# CanSharkV20.net
KiCad netlist of a schematic drawn in EAGLE
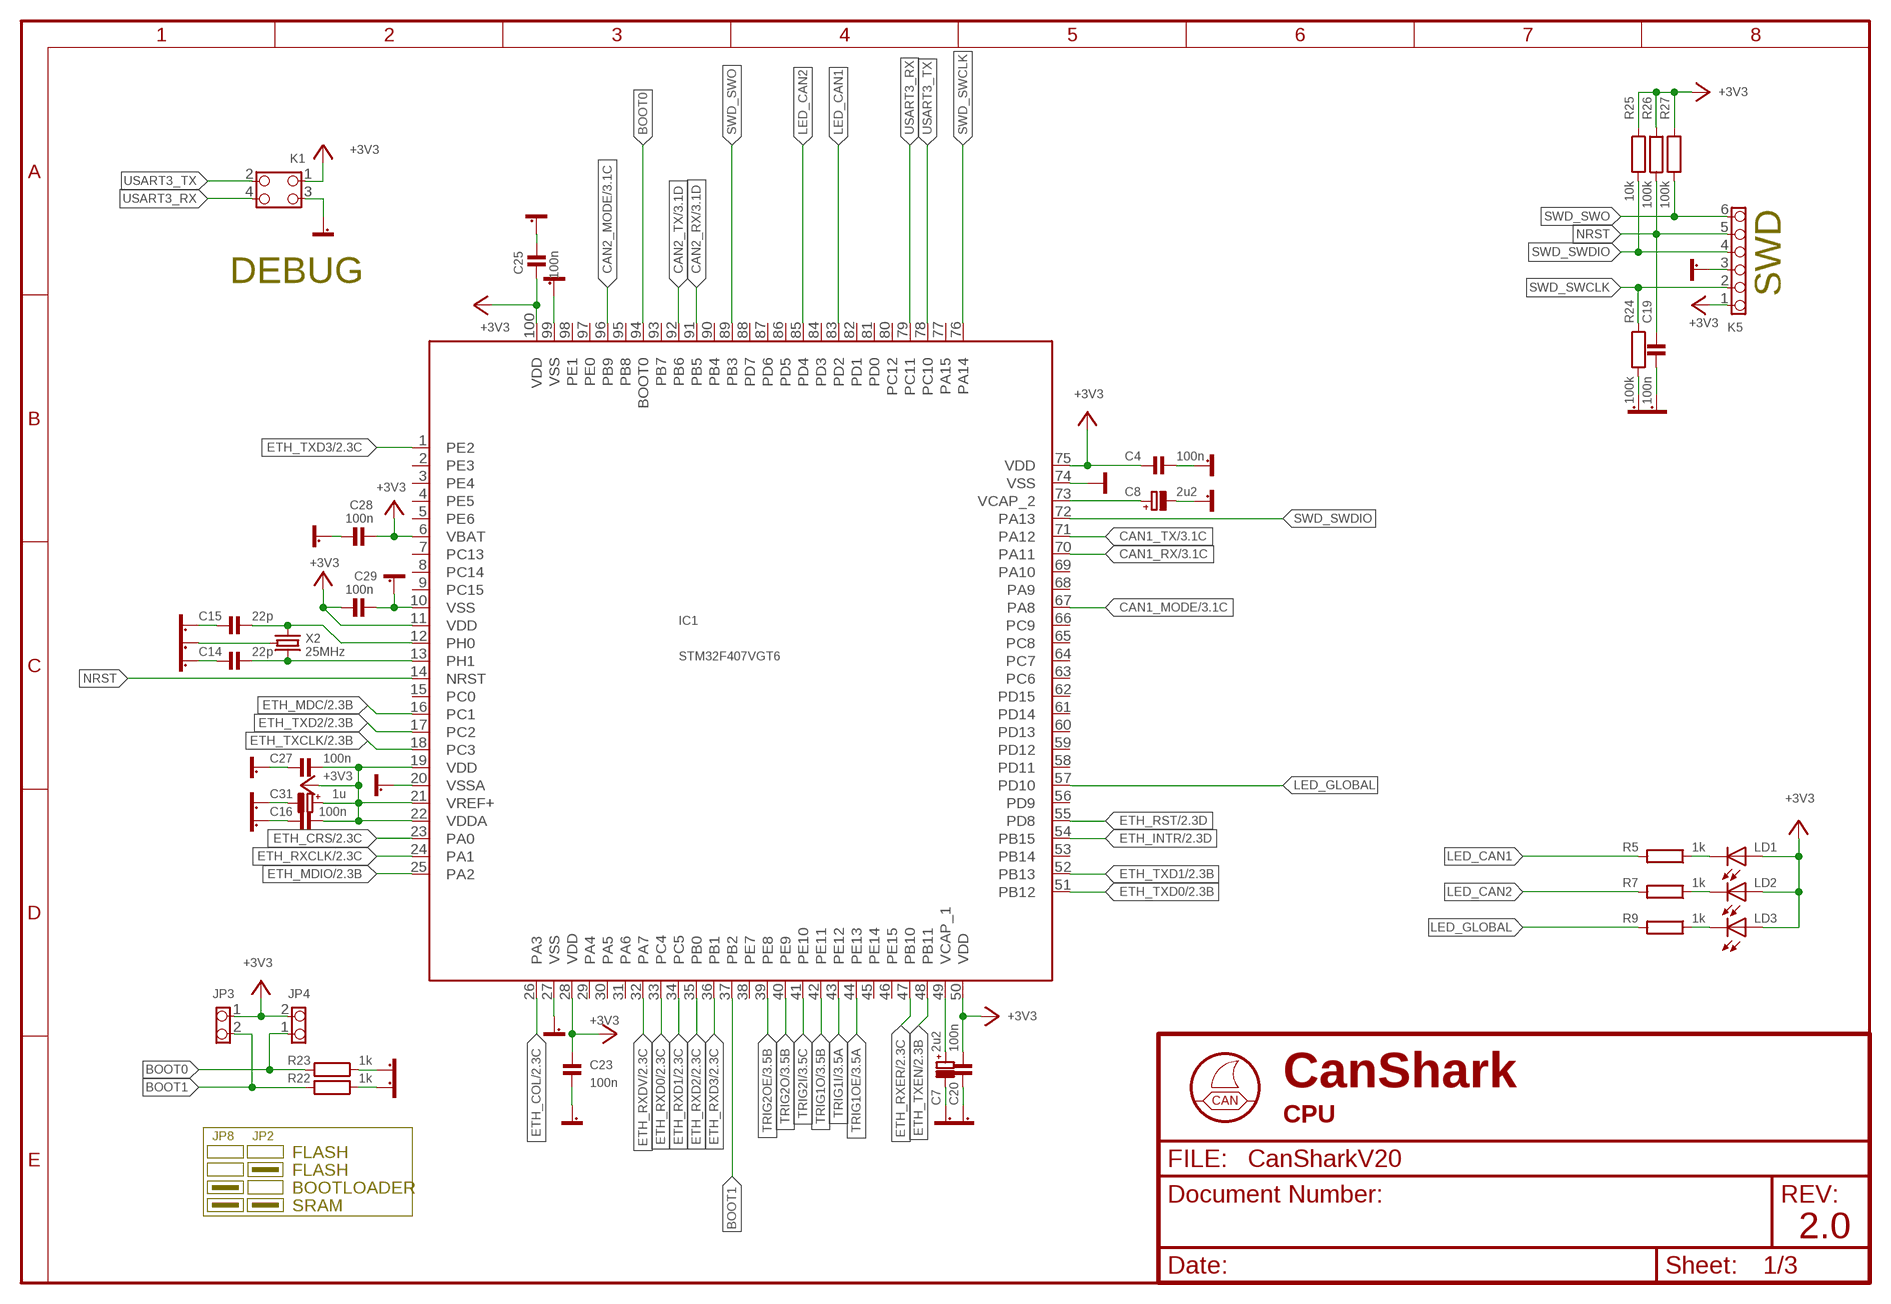
[diagram p0: schematic, sheet 1]
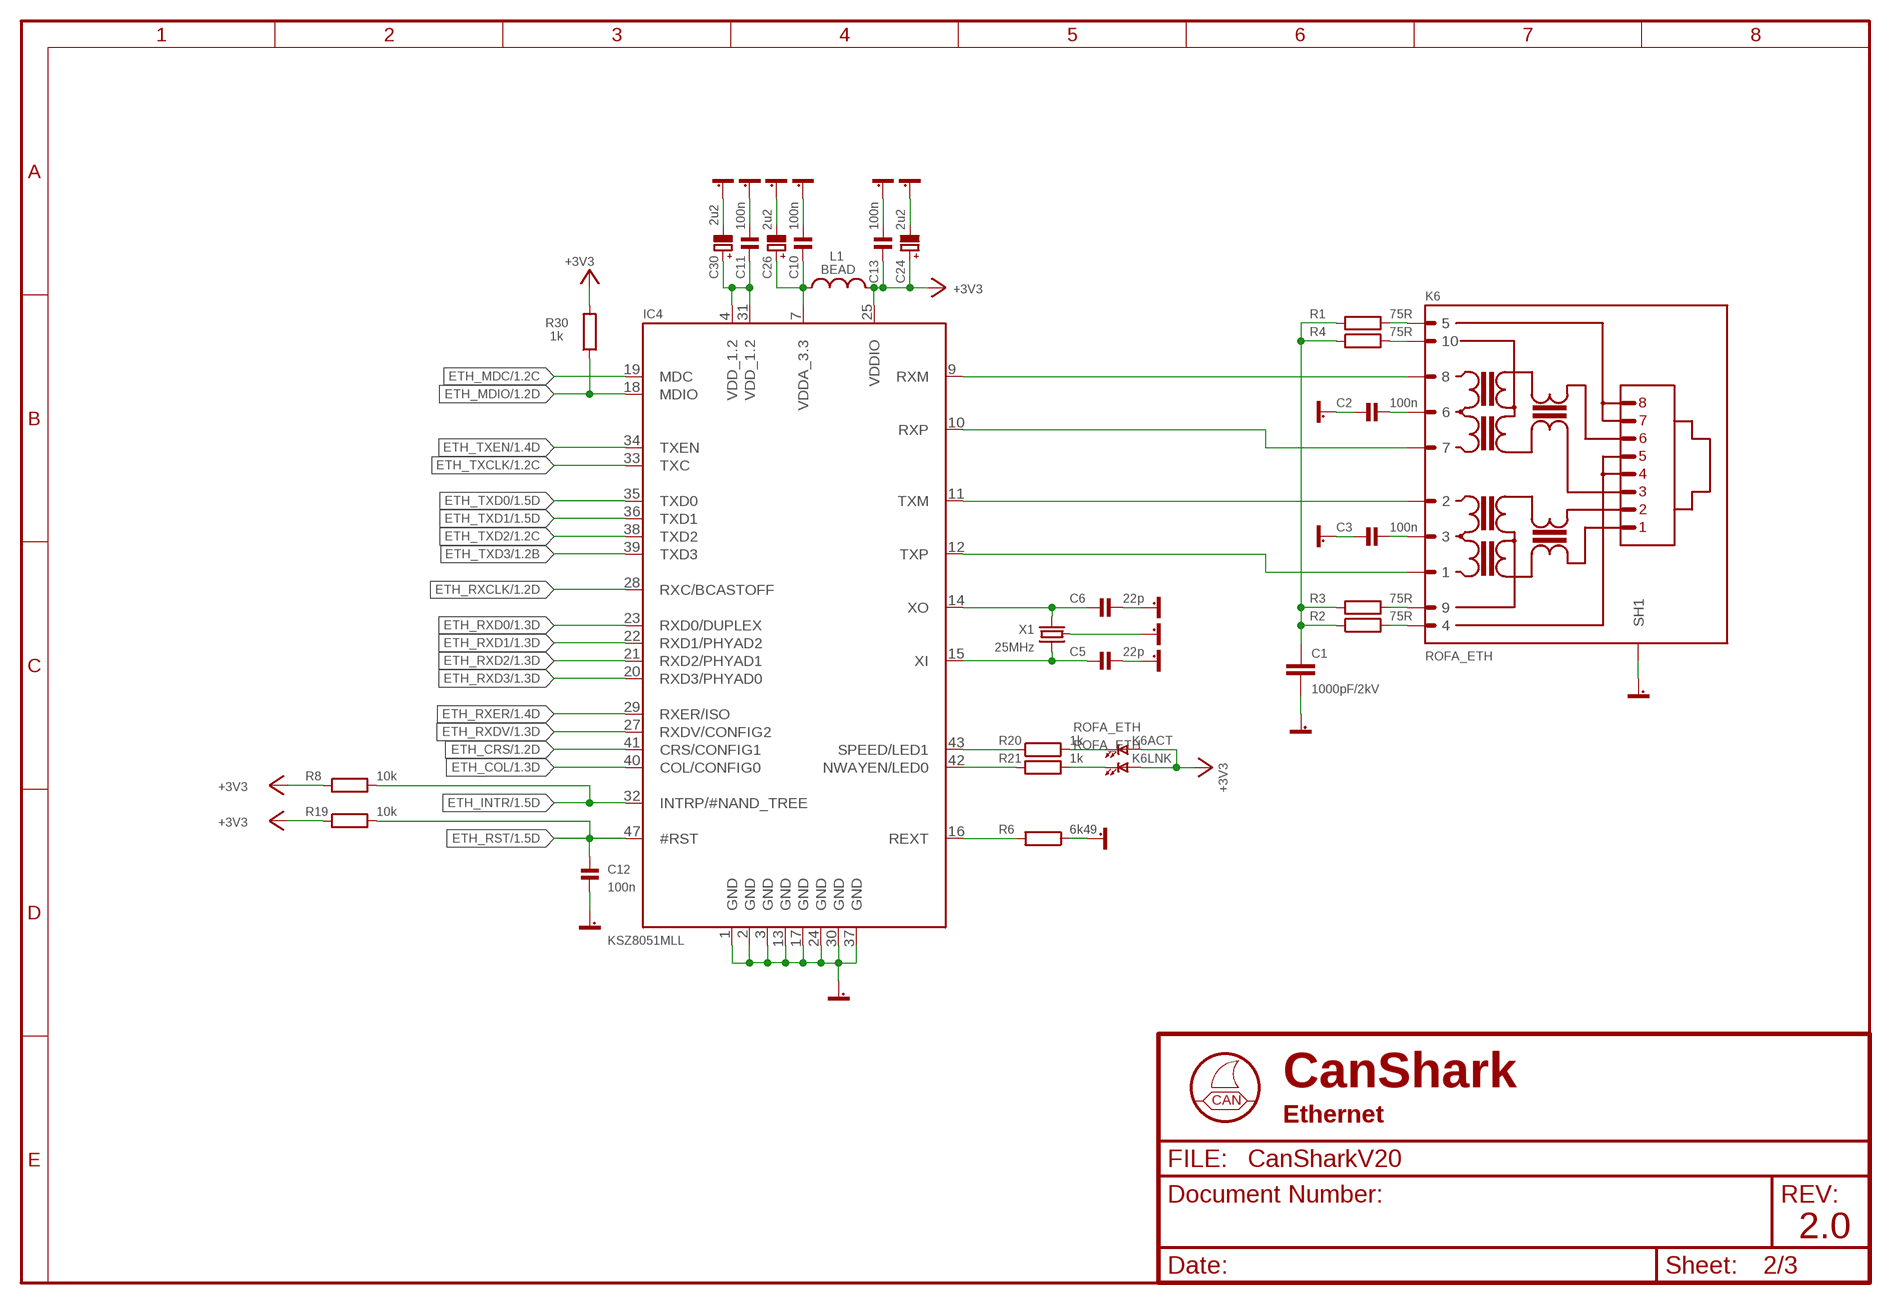
[diagram p1: schematic, sheet 2]
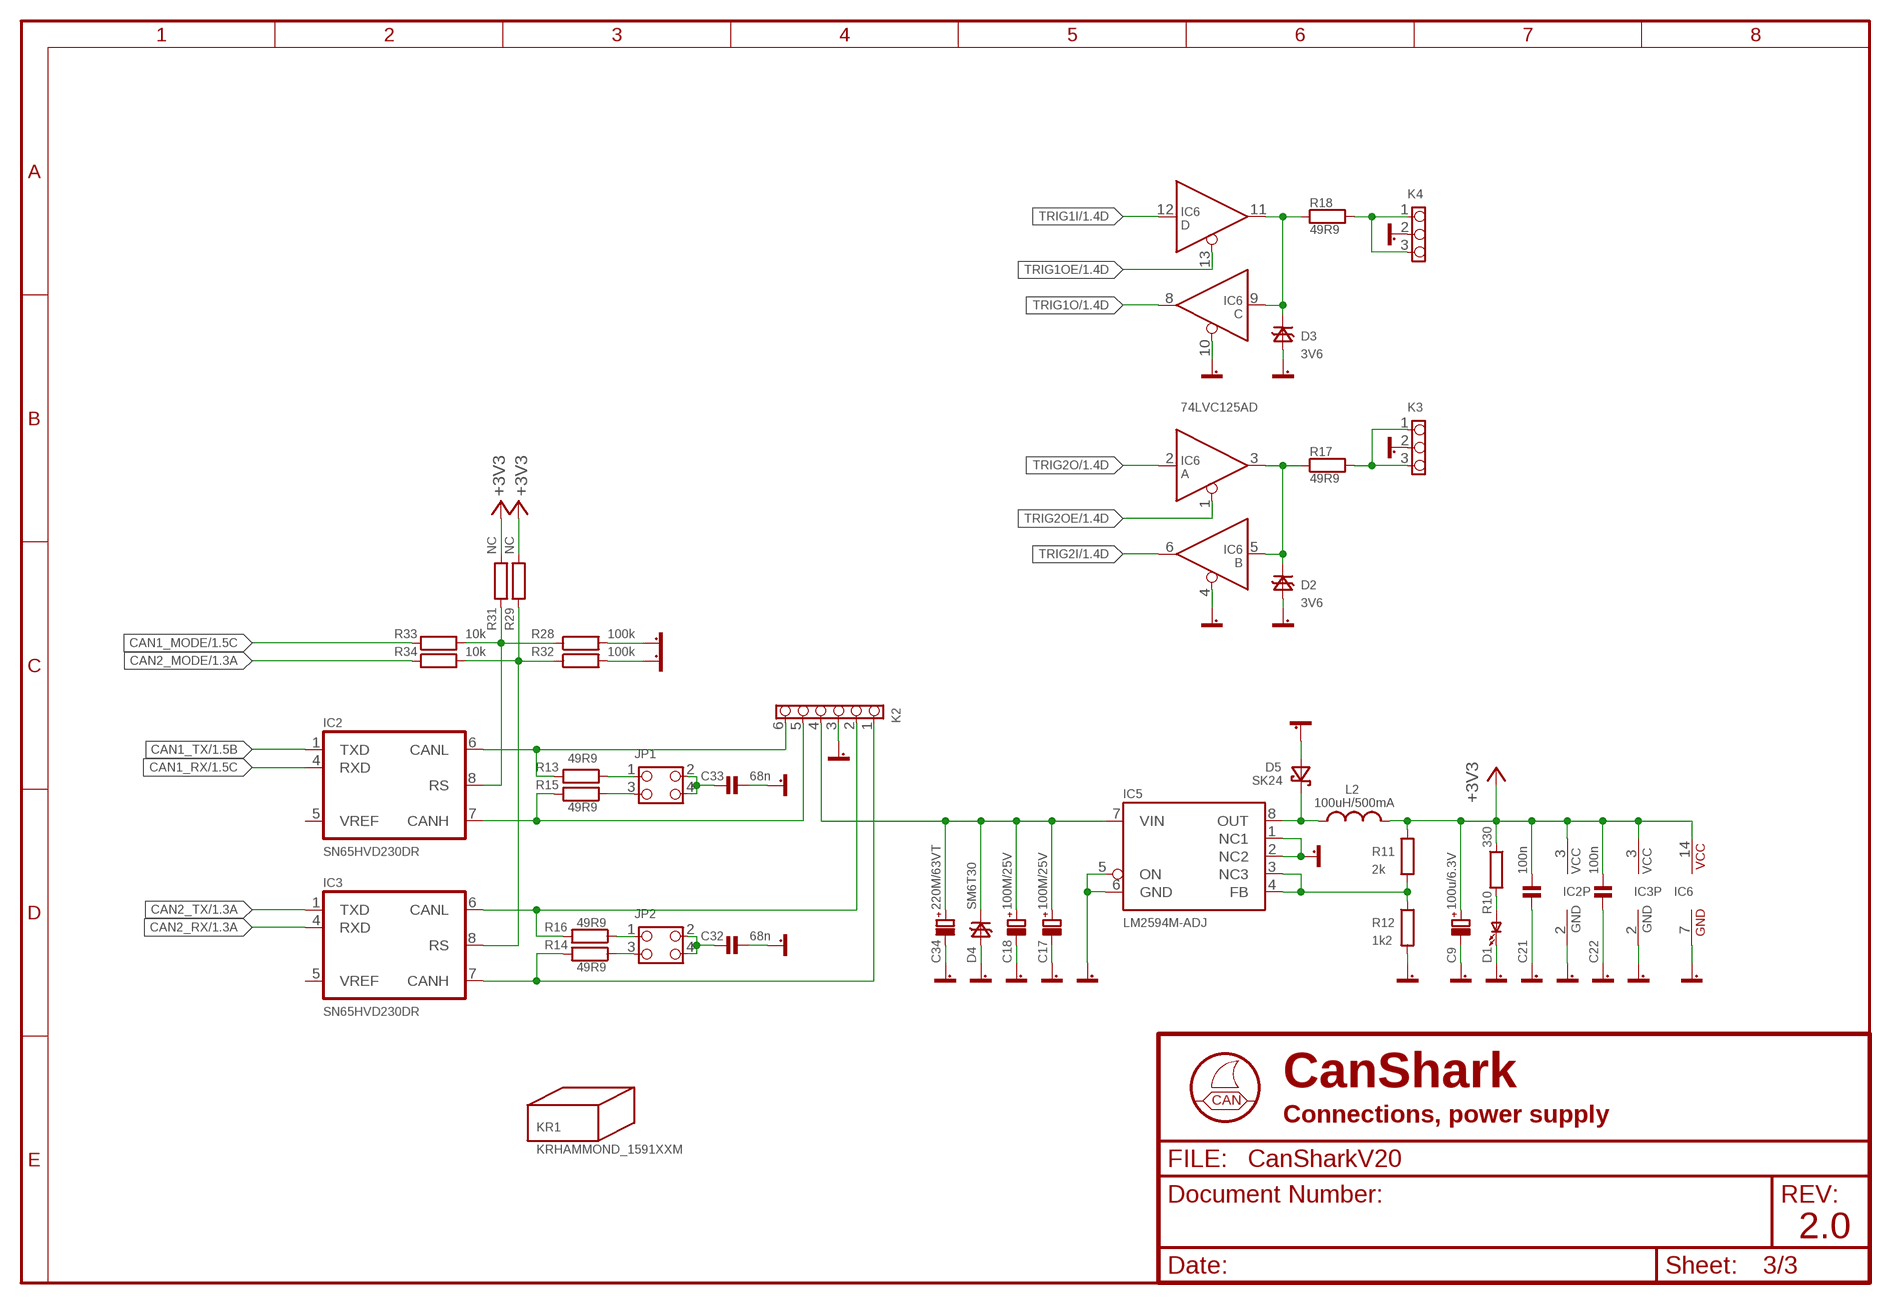
[diagram p2: schematic, sheet 3]

(export (version "E")
  (design (tool "Eeschema 10.0.6"))
  (components
    (comp (ref "C4")
      (value "100n")
      (footprint "eagle-import:0603")
      (libsource (lib "eagle-import") (part "C0603"))
    )
    (comp (ref "C7")
      (value "2u2")
      (footprint "eagle-import:CT3216A")
      (libsource (lib "eagle-import") (part "CECT3216"))
    )
    (comp (ref "C8")
      (value "2u2")
      (footprint "eagle-import:CT3216A")
      (libsource (lib "eagle-import") (part "CECT3216"))
    )
    (comp (ref "C14")
      (value "22p")
      (footprint "eagle-import:0603")
      (libsource (lib "eagle-import") (part "C0603"))
    )
    (comp (ref "C15")
      (value "22p")
      (footprint "eagle-import:0603")
      (libsource (lib "eagle-import") (part "C0603"))
    )
    (comp (ref "C16")
      (value "100n")
      (footprint "eagle-import:0603")
      (libsource (lib "eagle-import") (part "C0603"))
    )
    (comp (ref "C19")
      (value "100n")
      (footprint "eagle-import:0603")
      (libsource (lib "eagle-import") (part "C0603"))
    )
    (comp (ref "C20")
      (value "100n")
      (footprint "eagle-import:0603")
      (libsource (lib "eagle-import") (part "C0603"))
    )
    (comp (ref "C23")
      (value "100n")
      (footprint "eagle-import:0603")
      (libsource (lib "eagle-import") (part "C0603"))
    )
    (comp (ref "C25")
      (value "100n")
      (footprint "eagle-import:0603")
      (libsource (lib "eagle-import") (part "C0603"))
    )
    (comp (ref "C27")
      (value "100n")
      (footprint "eagle-import:0603")
      (libsource (lib "eagle-import") (part "C0603"))
    )
    (comp (ref "C28")
      (value "100n")
      (footprint "eagle-import:0603")
      (libsource (lib "eagle-import") (part "C0603"))
    )
    (comp (ref "C29")
      (value "100n")
      (footprint "eagle-import:0603")
      (libsource (lib "eagle-import") (part "C0603"))
    )
    (comp (ref "C31")
      (value "1u")
      (footprint "eagle-import:CT3216A")
      (libsource (lib "eagle-import") (part "CECT3216"))
    )
    (comp (ref "IC1")
      (value "STM32F407VGT6")
      (footprint "eagle-import:LQFP100")
      (libsource (lib "eagle-import") (part "STM32F4V07"))
    )
    (comp (ref "JP3")
      (value "PINHD-1X2")
      (footprint "eagle-import:1X02_254")
      (libsource (lib "eagle-import") (part "PINHD-1X2"))
    )
    (comp (ref "JP4")
      (value "PINHD-1X2")
      (footprint "eagle-import:1X02_254")
      (libsource (lib "eagle-import") (part "PINHD-1X2"))
    )
    (comp (ref "K1")
      (value "PINHD-2X2")
      (footprint "eagle-import:2X02_254")
      (libsource (lib "eagle-import") (part "PINHD-2X2"))
    )
    (comp (ref "K5")
      (value "PINHD-1X6")
      (footprint "eagle-import:1X06_254")
      (libsource (lib "eagle-import") (part "PINHD-1X6"))
    )
    (comp (ref "LD1")
      (value "TLLG4400")
      (footprint "eagle-import:LED3MM")
      (fields (field (name "MF") "VISHAY SEMICONDUCTOR"))
      (libsource (lib "eagle-import") (part "TLLG4400"))
    )
    (comp (ref "LD2")
      (value "TLLG4400")
      (footprint "eagle-import:LED3MM")
      (fields (field (name "MF") "VISHAY SEMICONDUCTOR"))
      (libsource (lib "eagle-import") (part "TLLG4400"))
    )
    (comp (ref "LD3")
      (value "TLLG4400")
      (footprint "eagle-import:LED3MM")
      (fields (field (name "MF") "VISHAY SEMICONDUCTOR"))
      (libsource (lib "eagle-import") (part "TLLG4400"))
    )
    (comp (ref "R5")
      (value "1k")
      (footprint "eagle-import:0603")
      (libsource (lib "eagle-import") (part "R_R0603"))
    )
    (comp (ref "R7")
      (value "1k")
      (footprint "eagle-import:0603")
      (libsource (lib "eagle-import") (part "R_R0603"))
    )
    (comp (ref "R9")
      (value "1k")
      (footprint "eagle-import:0603")
      (libsource (lib "eagle-import") (part "R_R0603"))
    )
    (comp (ref "R22")
      (value "1k")
      (footprint "eagle-import:0603")
      (libsource (lib "eagle-import") (part "R_R0603"))
    )
    (comp (ref "R23")
      (value "1k")
      (footprint "eagle-import:0603")
      (libsource (lib "eagle-import") (part "R_R0603"))
    )
    (comp (ref "R24")
      (value "100k")
      (footprint "eagle-import:0603")
      (libsource (lib "eagle-import") (part "R_R0603"))
    )
    (comp (ref "R25")
      (value "100k")
      (footprint "eagle-import:0603")
      (libsource (lib "eagle-import") (part "R_R0603"))
    )
    (comp (ref "R26")
      (value "10k")
      (footprint "eagle-import:0603")
      (libsource (lib "eagle-import") (part "R_R0603"))
    )
    (comp (ref "R27")
      (value "100k")
      (footprint "eagle-import:0603")
      (libsource (lib "eagle-import") (part "R_R0603"))
    )
    (comp (ref "X2")
      (value "25MHz")
      (footprint "eagle-import:X_XT324")
      (libsource (lib "eagle-import") (part "X_GND_XT324"))
    )
    (comp (ref "C1")
      (value "1000pF/2kV")
      (footprint "eagle-import:SMD1206")
      (libsource (lib "eagle-import") (part "KERAMICKYSMD1206"))
    )
    (comp (ref "C2")
      (value "100n")
      (footprint "eagle-import:0603")
      (libsource (lib "eagle-import") (part "C0603"))
    )
    (comp (ref "C3")
      (value "100n")
      (footprint "eagle-import:0603")
      (libsource (lib "eagle-import") (part "C0603"))
    )
    (comp (ref "C5")
      (value "22p")
      (footprint "eagle-import:0603")
      (libsource (lib "eagle-import") (part "C0603"))
    )
    (comp (ref "C6")
      (value "22p")
      (footprint "eagle-import:0603")
      (libsource (lib "eagle-import") (part "C0603"))
    )
    (comp (ref "C10")
      (value "100n")
      (footprint "eagle-import:0603")
      (libsource (lib "eagle-import") (part "C0603"))
    )
    (comp (ref "C11")
      (value "100n")
      (footprint "eagle-import:0603")
      (libsource (lib "eagle-import") (part "C0603"))
    )
    (comp (ref "C12")
      (value "100n")
      (footprint "eagle-import:0603")
      (libsource (lib "eagle-import") (part "C0603"))
    )
    (comp (ref "C13")
      (value "100n")
      (footprint "eagle-import:0603")
      (libsource (lib "eagle-import") (part "C0603"))
    )
    (comp (ref "C24")
      (value "2u2")
      (footprint "eagle-import:CT3216A")
      (libsource (lib "eagle-import") (part "CECT3216"))
    )
    (comp (ref "C26")
      (value "2u2")
      (footprint "eagle-import:CT3216A")
      (libsource (lib "eagle-import") (part "CECT3216"))
    )
    (comp (ref "C30")
      (value "2u2")
      (footprint "eagle-import:CT3216A")
      (libsource (lib "eagle-import") (part "CECT3216"))
    )
    (comp (ref "IC4")
      (value "KSZ8051MLL")
      (footprint "eagle-import:LQFP48")
      (libsource (lib "eagle-import") (part "KSZ8051MLL"))
    )
    (comp (ref "K6")
      (value "ROFA_ETH")
      (footprint "eagle-import:RJ45_TRAFO")
      (libsource (lib "eagle-import") (part "RJ45_TRAFO"))
    )
    (comp (ref "L1")
      (value "BEAD")
      (footprint "eagle-import:1206")
      (libsource (lib "eagle-import") (part "L1206"))
    )
    (comp (ref "R1")
      (value "75R")
      (footprint "eagle-import:0603")
      (libsource (lib "eagle-import") (part "R_R0603"))
    )
    (comp (ref "R2")
      (value "75R")
      (footprint "eagle-import:0603")
      (libsource (lib "eagle-import") (part "R_R0603"))
    )
    (comp (ref "R3")
      (value "75R")
      (footprint "eagle-import:0603")
      (libsource (lib "eagle-import") (part "R_R0603"))
    )
    (comp (ref "R4")
      (value "75R")
      (footprint "eagle-import:0603")
      (libsource (lib "eagle-import") (part "R_R0603"))
    )
    (comp (ref "R6")
      (value "6k49")
      (footprint "eagle-import:0603")
      (libsource (lib "eagle-import") (part "R_R0603"))
    )
    (comp (ref "R8")
      (value "10k")
      (footprint "eagle-import:0603")
      (libsource (lib "eagle-import") (part "R_R0603"))
    )
    (comp (ref "R19")
      (value "10k")
      (footprint "eagle-import:0603")
      (libsource (lib "eagle-import") (part "R_R0603"))
    )
    (comp (ref "R20")
      (value "1k")
      (footprint "eagle-import:0603")
      (libsource (lib "eagle-import") (part "R_R0603"))
    )
    (comp (ref "R21")
      (value "1k")
      (footprint "eagle-import:0603")
      (libsource (lib "eagle-import") (part "R_R0603"))
    )
    (comp (ref "R30")
      (value "1k")
      (footprint "eagle-import:0603")
      (libsource (lib "eagle-import") (part "R_R0603"))
    )
    (comp (ref "X1")
      (value "25MHz")
      (footprint "eagle-import:X_XT324")
      (libsource (lib "eagle-import") (part "X_GND_XT324"))
    )
    (comp (ref "C9")
      (value "100u/6.3V")
      (footprint "eagle-import:CT3528B")
      (libsource (lib "eagle-import") (part "CECT3528"))
    )
    (comp (ref "C17")
      (value "100M/25V")
      (footprint "eagle-import:CT7343D")
      (libsource (lib "eagle-import") (part "CECT7343"))
    )
    (comp (ref "C18")
      (value "100M/25V")
      (footprint "eagle-import:CT7343D")
      (libsource (lib "eagle-import") (part "CECT7343"))
    )
    (comp (ref "C21")
      (value "100n")
      (footprint "eagle-import:0603")
      (libsource (lib "eagle-import") (part "C0603"))
    )
    (comp (ref "C22")
      (value "100n")
      (footprint "eagle-import:0603")
      (libsource (lib "eagle-import") (part "C0603"))
    )
    (comp (ref "C32")
      (value "68n")
      (footprint "eagle-import:0805")
      (libsource (lib "eagle-import") (part "C0805"))
    )
    (comp (ref "C33")
      (value "68n")
      (footprint "eagle-import:0805")
      (libsource (lib "eagle-import") (part "C0805"))
    )
    (comp (ref "C34")
      (value "220M/63VT")
      (footprint "eagle-import:CE_D10L13_R")
      (libsource (lib "eagle-import") (part "CE_D10L13_R"))
    )
    (comp (ref "D1")
      (value "LED0805")
      (footprint "eagle-import:LED_0805")
      (libsource (lib "eagle-import") (part "LED0805"))
    )
    (comp (ref "D2")
      (value "3V6")
      (footprint "eagle-import:D_SMA")
      (libsource (lib "eagle-import") (part "!discrete_D_TRANSIL_SMA"))
    )
    (comp (ref "D3")
      (value "3V6")
      (footprint "eagle-import:D_SMA")
      (libsource (lib "eagle-import") (part "!discrete_D_TRANSIL_SMA"))
    )
    (comp (ref "D4")
      (value "SM6T30")
      (footprint "eagle-import:D_SMB")
      (libsource (lib "eagle-import") (part "D_TRANSIL_SMB"))
    )
    (comp (ref "D5")
      (value "SK24")
      (footprint "eagle-import:D_SMB")
      (libsource (lib "eagle-import") (part "D_SCHOTKY_SMB"))
    )
    (comp (ref "IC2")
      (value "SN65HVD230DR")
      (footprint "eagle-import:SO08")
      (libsource (lib "eagle-import") (part "MCP2551/S"))
    )
    (comp (ref "IC3")
      (value "SN65HVD230DR")
      (footprint "eagle-import:SO08")
      (libsource (lib "eagle-import") (part "MCP2551/S"))
    )
    (comp (ref "IC5")
      (value "LM2594M-ADJ")
      (footprint "eagle-import:SO08")
      (libsource (lib "eagle-import") (part "LM2594_SO"))
    )
    (comp (ref "IC6")
      (value "74LVC125AD")
      (footprint "eagle-import:SO14")
      (libsource (lib "eagle-import") (part "74125ADLVC"))
    )
    (comp (ref "JP1")
      (value "PINHD-2X2_254_EDGE")
      (footprint "eagle-import:2X02_254_EDGE")
      (libsource (lib "eagle-import") (part "PINHD-2X2_254_EDGE"))
    )
    (comp (ref "JP2")
      (value "PINHD-2X2_254_EDGE")
      (footprint "eagle-import:2X02_254_EDGE")
      (libsource (lib "eagle-import") (part "PINHD-2X2_254_EDGE"))
    )
    (comp (ref "K2")
      (value "PINHD-1X6_381_V")
      (footprint "eagle-import:1X06_381_V")
      (libsource (lib "eagle-import") (part "PINHD-1X6_381_V"))
    )
    (comp (ref "K3")
      (value "PINHD-1X3")
      (footprint "eagle-import:1X03_254")
      (libsource (lib "eagle-import") (part "PINHD-1X3"))
    )
    (comp (ref "K4")
      (value "PINHD-1X3")
      (footprint "eagle-import:1X03_254")
      (libsource (lib "eagle-import") (part "PINHD-1X3"))
    )
    (comp (ref "KR1")
      (value "KRHAMMOND_1591XXM")
      (footprint "eagle-import:HAMMOND_1591XXM")
      (libsource (lib "eagle-import") (part "KRHAMMOND_1591XXM"))
    )
    (comp (ref "L2")
      (value "100uH/500mA")
      (footprint "eagle-import:L_MLC12XX")
      (libsource (lib "eagle-import") (part "L_MLC12XX"))
    )
    (comp (ref "R10")
      (value "330")
      (footprint "eagle-import:0603")
      (libsource (lib "eagle-import") (part "R_R0603"))
    )
    (comp (ref "R11")
      (value "2k")
      (footprint "eagle-import:0603")
      (libsource (lib "eagle-import") (part "R_R0603"))
    )
    (comp (ref "R12")
      (value "1k2")
      (footprint "eagle-import:0603")
      (libsource (lib "eagle-import") (part "R_R0603"))
    )
    (comp (ref "R13")
      (value "49R9")
      (footprint "eagle-import:0805")
      (libsource (lib "eagle-import") (part "R_R0805"))
    )
    (comp (ref "R14")
      (value "49R9")
      (footprint "eagle-import:0805")
      (libsource (lib "eagle-import") (part "R_R0805"))
    )
    (comp (ref "R15")
      (value "49R9")
      (footprint "eagle-import:0805")
      (libsource (lib "eagle-import") (part "R_R0805"))
    )
    (comp (ref "R16")
      (value "49R9")
      (footprint "eagle-import:0805")
      (libsource (lib "eagle-import") (part "R_R0805"))
    )
    (comp (ref "R17")
      (value "49R9")
      (footprint "eagle-import:0805")
      (libsource (lib "eagle-import") (part "R_R0805"))
    )
    (comp (ref "R18")
      (value "49R9")
      (footprint "eagle-import:0805")
      (libsource (lib "eagle-import") (part "R_R0805"))
    )
    (comp (ref "R28")
      (value "100k")
      (footprint "eagle-import:0603")
      (libsource (lib "eagle-import") (part "R_R0603"))
    )
    (comp (ref "R29")
      (value "NC")
      (footprint "eagle-import:0603")
      (libsource (lib "eagle-import") (part "R_R0603"))
    )
    (comp (ref "R31")
      (value "NC")
      (footprint "eagle-import:0603")
      (libsource (lib "eagle-import") (part "R_R0603"))
    )
    (comp (ref "R32")
      (value "100k")
      (footprint "eagle-import:0603")
      (libsource (lib "eagle-import") (part "R_R0603"))
    )
    (comp (ref "R33")
      (value "10k")
      (footprint "eagle-import:0603")
      (libsource (lib "eagle-import") (part "R_R0603"))
    )
    (comp (ref "R34")
      (value "10k")
      (footprint "eagle-import:0603")
      (libsource (lib "eagle-import") (part "R_R0603"))
    )
  )
  (nets
    (net (code "1") (name "+3V3") (class "Default")
      (node (ref "C13") (pin "2") (pinfunction "2_2") (pintype "passive"))
      (node (ref "C16") (pin "1") (pinfunction "1_1") (pintype "passive"))
      (node (ref "C20") (pin "1") (pinfunction "1_1") (pintype "passive"))
      (node (ref "C21") (pin "1") (pinfunction "1_1") (pintype "passive"))
      (node (ref "C22") (pin "1") (pinfunction "1_1") (pintype "passive"))
      (node (ref "C23") (pin "1") (pinfunction "1_1") (pintype "passive"))
      (node (ref "C24") (pin "+") (pinfunction "+_+") (pintype "passive"))
      (node (ref "C25") (pin "2") (pinfunction "2_2") (pintype "passive"))
      (node (ref "C27") (pin "1") (pinfunction "1_1") (pintype "passive"))
      (node (ref "C28") (pin "2") (pinfunction "2_2") (pintype "passive"))
      (node (ref "C29") (pin "2") (pinfunction "2_2") (pintype "passive"))
      (node (ref "C31") (pin "+") (pinfunction "+_+") (pintype "passive"))
      (node (ref "C4") (pin "2") (pinfunction "2_2") (pintype "passive"))
      (node (ref "C9") (pin "+") (pinfunction "+_+") (pintype "passive"))
      (node (ref "IC1") (pin "100") (pinfunction "VDD_100") (pintype "passive"))
      (node (ref "IC1") (pin "11") (pinfunction "VDD_11") (pintype "passive"))
      (node (ref "IC1") (pin "19") (pinfunction "VDD_19") (pintype "passive"))
      (node (ref "IC1") (pin "21") (pinfunction "VREF+_21") (pintype "passive"))
      (node (ref "IC1") (pin "22") (pinfunction "VDDA_22") (pintype "passive"))
      (node (ref "IC1") (pin "28") (pinfunction "VDD_28") (pintype "passive"))
      (node (ref "IC1") (pin "50") (pinfunction "VDD_50") (pintype "passive"))
      (node (ref "IC1") (pin "6") (pinfunction "VBAT_6") (pintype "passive"))
      (node (ref "IC1") (pin "75") (pinfunction "VDD_75") (pintype "passive"))
      (node (ref "IC2") (pin "3") (pinfunction "VCC_3") (pintype "power_in"))
      (node (ref "IC3") (pin "3") (pinfunction "VCC_3") (pintype "power_in"))
      (node (ref "IC4") (pin "25") (pinfunction "VDDIO_25") (pintype "passive"))
      (node (ref "IC6") (pin "14") (pinfunction "VCC_14") (pintype "passive"))
      (node (ref "JP3") (pin "1") (pinfunction "1_1") (pintype "passive"))
      (node (ref "JP4") (pin "2") (pinfunction "2_2") (pintype "passive"))
      (node (ref "K1") (pin "1") (pinfunction "1_1") (pintype "passive"))
      (node (ref "K5") (pin "1") (pinfunction "1_1") (pintype "passive"))
      (node (ref "K6") (pin "A_G") (pinfunction "A_A_G") (pintype "passive"))
      (node (ref "K6") (pin "A_Y") (pinfunction "A_A_Y") (pintype "passive"))
      (node (ref "L1") (pin "1") (pinfunction "1_1") (pintype "passive"))
      (node (ref "L2") (pin "2") (pinfunction "1_2") (pintype "passive"))
      (node (ref "LD1") (pin "A") (pinfunction "A_A") (pintype "passive"))
      (node (ref "LD2") (pin "A") (pinfunction "A_A") (pintype "passive"))
      (node (ref "LD3") (pin "A") (pinfunction "A_A") (pintype "passive"))
      (node (ref "R10") (pin "1") (pinfunction "1_1") (pintype "passive"))
      (node (ref "R11") (pin "1") (pinfunction "1_1") (pintype "passive"))
      (node (ref "R19") (pin "1") (pinfunction "1_1") (pintype "passive"))
      (node (ref "R25") (pin "1") (pinfunction "1_1") (pintype "passive"))
      (node (ref "R26") (pin "2") (pinfunction "2_2") (pintype "passive"))
      (node (ref "R27") (pin "1") (pinfunction "1_1") (pintype "passive"))
      (node (ref "R29") (pin "1") (pinfunction "1_1") (pintype "passive"))
      (node (ref "R30") (pin "2") (pinfunction "2_2") (pintype "passive"))
      (node (ref "R31") (pin "1") (pinfunction "1_1") (pintype "passive"))
      (node (ref "R8") (pin "1") (pinfunction "1_1") (pintype "passive"))
    )
    (net (code "2") (name "BOOT0") (class "Default")
      (node (ref "IC1") (pin "94") (pinfunction "BOOT0_94") (pintype "passive"))
      (node (ref "JP4") (pin "1") (pinfunction "1_1") (pintype "passive"))
      (node (ref "R23") (pin "2") (pinfunction "2_2") (pintype "passive"))
    )
    (net (code "3") (name "BOOT1") (class "Default")
      (node (ref "IC1") (pin "37") (pinfunction "PB2_37") (pintype "passive"))
      (node (ref "JP3") (pin "2") (pinfunction "2_2") (pintype "passive"))
      (node (ref "R22") (pin "2") (pinfunction "2_2") (pintype "passive"))
    )
    (net (code "4") (name "CAN1_MODE") (class "Default")
      (node (ref "IC1") (pin "67") (pinfunction "PA8_67") (pintype "passive"))
      (node (ref "R33") (pin "1") (pinfunction "1_1") (pintype "passive"))
    )
    (net (code "5") (name "CAN1_RX") (class "Default")
      (node (ref "IC1") (pin "70") (pinfunction "PA11_70") (pintype "passive"))
      (node (ref "IC2") (pin "4") (pinfunction "RXD_4") (pintype "output"))
    )
    (net (code "6") (name "CAN1_TX") (class "Default")
      (node (ref "IC1") (pin "71") (pinfunction "PA12_71") (pintype "passive"))
      (node (ref "IC2") (pin "1") (pinfunction "TXD_1") (pintype "input"))
    )
    (net (code "7") (name "CAN2_MODE") (class "Default")
      (node (ref "IC1") (pin "96") (pinfunction "PB9_96") (pintype "passive"))
      (node (ref "R34") (pin "1") (pinfunction "1_1") (pintype "passive"))
    )
    (net (code "8") (name "CAN2_RX") (class "Default")
      (node (ref "IC1") (pin "91") (pinfunction "PB5_91") (pintype "passive"))
      (node (ref "IC3") (pin "4") (pinfunction "RXD_4") (pintype "output"))
    )
    (net (code "9") (name "CAN2_TX") (class "Default")
      (node (ref "IC1") (pin "92") (pinfunction "PB6_92") (pintype "passive"))
      (node (ref "IC3") (pin "1") (pinfunction "TXD_1") (pintype "input"))
    )
    (net (code "10") (name "ETH_COL") (class "Default")
      (node (ref "IC1") (pin "26") (pinfunction "PA3_26") (pintype "passive"))
      (node (ref "IC4") (pin "40") (pinfunction "COL/CONFIG0_40") (pintype "passive"))
    )
    (net (code "11") (name "ETH_CRS") (class "Default")
      (node (ref "IC1") (pin "23") (pinfunction "PA0_23") (pintype "passive"))
      (node (ref "IC4") (pin "41") (pinfunction "CRS/CONFIG1_41") (pintype "passive"))
    )
    (net (code "12") (name "ETH_INTR") (class "Default")
      (node (ref "IC1") (pin "54") (pinfunction "PB15_54") (pintype "passive"))
      (node (ref "IC4") (pin "32") (pinfunction "INTRP/#NAND_TREE_32") (pintype "passive"))
      (node (ref "R8") (pin "2") (pinfunction "2_2") (pintype "passive"))
    )
    (net (code "13") (name "ETH_MDC") (class "Default")
      (node (ref "IC1") (pin "16") (pinfunction "PC1_16") (pintype "passive"))
      (node (ref "IC4") (pin "19") (pinfunction "MDC_19") (pintype "passive"))
    )
    (net (code "14") (name "ETH_MDIO") (class "Default")
      (node (ref "IC1") (pin "25") (pinfunction "PA2_25") (pintype "passive"))
      (node (ref "IC4") (pin "18") (pinfunction "MDIO_18") (pintype "passive"))
      (node (ref "R30") (pin "1") (pinfunction "1_1") (pintype "passive"))
    )
    (net (code "15") (name "ETH_RST") (class "Default")
      (node (ref "C12") (pin "1") (pinfunction "1_1") (pintype "passive"))
      (node (ref "IC1") (pin "55") (pinfunction "PD8_55") (pintype "passive"))
      (node (ref "IC4") (pin "47") (pinfunction "#RST_47") (pintype "passive"))
      (node (ref "R19") (pin "2") (pinfunction "2_2") (pintype "passive"))
    )
    (net (code "16") (name "ETH_RXCLK") (class "Default")
      (node (ref "IC1") (pin "24") (pinfunction "PA1_24") (pintype "passive"))
      (node (ref "IC4") (pin "28") (pinfunction "RXC/BCASTOFF_28") (pintype "passive"))
    )
    (net (code "17") (name "ETH_RXD0") (class "Default")
      (node (ref "IC1") (pin "33") (pinfunction "PC4_33") (pintype "passive"))
      (node (ref "IC4") (pin "23") (pinfunction "RXD0/DUPLEX_23") (pintype "passive"))
    )
    (net (code "18") (name "ETH_RXD1") (class "Default")
      (node (ref "IC1") (pin "34") (pinfunction "PC5_34") (pintype "passive"))
      (node (ref "IC4") (pin "22") (pinfunction "RXD1/PHYAD2_22") (pintype "passive"))
    )
    (net (code "19") (name "ETH_RXD2") (class "Default")
      (node (ref "IC1") (pin "35") (pinfunction "PB0_35") (pintype "passive"))
      (node (ref "IC4") (pin "21") (pinfunction "RXD2/PHYAD1_21") (pintype "passive"))
    )
    (net (code "20") (name "ETH_RXD3") (class "Default")
      (node (ref "IC1") (pin "36") (pinfunction "PB1_36") (pintype "passive"))
      (node (ref "IC4") (pin "20") (pinfunction "RXD3/PHYAD0_20") (pintype "passive"))
    )
    (net (code "21") (name "ETH_RXDV") (class "Default")
      (node (ref "IC1") (pin "32") (pinfunction "PA7_32") (pintype "passive"))
      (node (ref "IC4") (pin "27") (pinfunction "RXDV/CONFIG2_27") (pintype "passive"))
    )
    (net (code "22") (name "ETH_RXER") (class "Default")
      (node (ref "IC1") (pin "47") (pinfunction "PB10_47") (pintype "passive"))
      (node (ref "IC4") (pin "29") (pinfunction "RXER/ISO_29") (pintype "passive"))
    )
    (net (code "23") (name "ETH_TXCLK") (class "Default")
      (node (ref "IC1") (pin "18") (pinfunction "PC3_18") (pintype "passive"))
      (node (ref "IC4") (pin "33") (pinfunction "TXC_33") (pintype "passive"))
    )
    (net (code "24") (name "ETH_TXD0") (class "Default")
      (node (ref "IC1") (pin "51") (pinfunction "PB12_51") (pintype "passive"))
      (node (ref "IC4") (pin "35") (pinfunction "TXD0_35") (pintype "passive"))
    )
    (net (code "25") (name "ETH_TXD1") (class "Default")
      (node (ref "IC1") (pin "52") (pinfunction "PB13_52") (pintype "passive"))
      (node (ref "IC4") (pin "36") (pinfunction "TXD1_36") (pintype "passive"))
    )
    (net (code "26") (name "ETH_TXD2") (class "Default")
      (node (ref "IC1") (pin "17") (pinfunction "PC2_17") (pintype "passive"))
      (node (ref "IC4") (pin "38") (pinfunction "TXD2_38") (pintype "passive"))
    )
    (net (code "27") (name "ETH_TXD3") (class "Default")
      (node (ref "IC1") (pin "1") (pinfunction "PE2_1") (pintype "passive"))
      (node (ref "IC4") (pin "39") (pinfunction "TXD3_39") (pintype "passive"))
    )
    (net (code "28") (name "ETH_TXEN") (class "Default")
      (node (ref "IC1") (pin "48") (pinfunction "PB11_48") (pintype "passive"))
      (node (ref "IC4") (pin "34") (pinfunction "TXEN_34") (pintype "passive"))
    )
    (net (code "29") (name "GND") (class "Default")
      (node (ref "IC1") (pin "74") (pinfunction "VSS_74") (pintype "passive"))
    )
    (net (code "30") (name "GND1") (class "Default")
      (node (ref "C1") (pin "2") (pinfunction "2_2") (pintype "passive"))
      (node (ref "C10") (pin "1") (pinfunction "1_1") (pintype "passive"))
      (node (ref "C11") (pin "1") (pinfunction "1_1") (pintype "passive"))
      (node (ref "C12") (pin "2") (pinfunction "2_2") (pintype "passive"))
      (node (ref "C13") (pin "1") (pinfunction "1_1") (pintype "passive"))
      (node (ref "C14") (pin "2") (pinfunction "2_2") (pintype "passive"))
      (node (ref "C15") (pin "2") (pinfunction "2_2") (pintype "passive"))
      (node (ref "C16") (pin "2") (pinfunction "2_2") (pintype "passive"))
      (node (ref "C17") (pin "-") (pinfunction "-_-") (pintype "passive"))
      (node (ref "C18") (pin "-") (pinfunction "-_-") (pintype "passive"))
      (node (ref "C19") (pin "2") (pinfunction "2_2") (pintype "passive"))
      (node (ref "C2") (pin "1") (pinfunction "1_1") (pintype "passive"))
      (node (ref "C20") (pin "2") (pinfunction "2_2") (pintype "passive"))
      (node (ref "C21") (pin "2") (pinfunction "2_2") (pintype "passive"))
      (node (ref "C22") (pin "2") (pinfunction "2_2") (pintype "passive"))
      (node (ref "C23") (pin "2") (pinfunction "2_2") (pintype "passive"))
      (node (ref "C24") (pin "-") (pinfunction "-_-") (pintype "passive"))
      (node (ref "C25") (pin "1") (pinfunction "1_1") (pintype "passive"))
      (node (ref "C26") (pin "-") (pinfunction "-_-") (pintype "passive"))
      (node (ref "C27") (pin "2") (pinfunction "2_2") (pintype "passive"))
      (node (ref "C28") (pin "1") (pinfunction "1_1") (pintype "passive"))
      (node (ref "C29") (pin "1") (pinfunction "1_1") (pintype "passive"))
      (node (ref "C3") (pin "1") (pinfunction "1_1") (pintype "passive"))
      (node (ref "C30") (pin "-") (pinfunction "-_-") (pintype "passive"))
      (node (ref "C31") (pin "-") (pinfunction "-_-") (pintype "passive"))
      (node (ref "C32") (pin "1") (pinfunction "1_1") (pintype "passive"))
      (node (ref "C33") (pin "1") (pinfunction "1_1") (pintype "passive"))
      (node (ref "C34") (pin "M") (pinfunction "-_M") (pintype "passive"))
      (node (ref "C4") (pin "1") (pinfunction "1_1") (pintype "passive"))
      (node (ref "C5") (pin "1") (pinfunction "1_1") (pintype "passive"))
      (node (ref "C6") (pin "1") (pinfunction "1_1") (pintype "passive"))
      (node (ref "C7") (pin "-") (pinfunction "-_-") (pintype "passive"))
      (node (ref "C8") (pin "-") (pinfunction "-_-") (pintype "passive"))
      (node (ref "C9") (pin "-") (pinfunction "-_-") (pintype "passive"))
      (node (ref "D1") (pin "K") (pinfunction "C_K") (pintype "passive"))
      (node (ref "D2") (pin "A") (pinfunction "A_A") (pintype "passive"))
      (node (ref "D3") (pin "A") (pinfunction "A_A") (pintype "passive"))
      (node (ref "D4") (pin "A") (pinfunction "A_A") (pintype "passive"))
      (node (ref "D5") (pin "A") (pinfunction "A_A") (pintype "passive"))
      (node (ref "IC1") (pin "10") (pinfunction "VSS_10") (pintype "passive"))
      (node (ref "IC1") (pin "20") (pinfunction "VSSA_20") (pintype "passive"))
      (node (ref "IC1") (pin "27") (pinfunction "VSS_27") (pintype "passive"))
      (node (ref "IC1") (pin "99") (pinfunction "VSS_99") (pintype "passive"))
      (node (ref "IC2") (pin "2") (pinfunction "GND_2") (pintype "power_in"))
      (node (ref "IC3") (pin "2") (pinfunction "GND_2") (pintype "power_in"))
      (node (ref "IC4") (pin "1") (pinfunction "GND_1") (pintype "power_in"))
      (node (ref "IC4") (pin "13") (pinfunction "GND_13") (pintype "power_in"))
      (node (ref "IC4") (pin "17") (pinfunction "GND_17") (pintype "power_in"))
      (node (ref "IC4") (pin "2") (pinfunction "GND_2") (pintype "power_in"))
      (node (ref "IC4") (pin "24") (pinfunction "GND_24") (pintype "power_in"))
      (node (ref "IC4") (pin "3") (pinfunction "GND_3") (pintype "power_in"))
      (node (ref "IC4") (pin "30") (pinfunction "GND_30") (pintype "power_in"))
      (node (ref "IC4") (pin "37") (pinfunction "GND_37") (pintype "power_in"))
      (node (ref "IC5") (pin "1") (pinfunction "NC1_1") (pintype "passive"))
      (node (ref "IC5") (pin "2") (pinfunction "NC2_2") (pintype "passive"))
      (node (ref "IC5") (pin "5") (pinfunction "ON_5") (pintype "passive"))
      (node (ref "IC5") (pin "6") (pinfunction "GND_6") (pintype "passive"))
      (node (ref "IC6") (pin "10") (pinfunction "OE_10") (pintype "input"))
      (node (ref "IC6") (pin "4") (pinfunction "OE_4") (pintype "input"))
      (node (ref "IC6") (pin "7") (pinfunction "GND_7") (pintype "passive"))
      (node (ref "K1") (pin "3") (pinfunction "3_3") (pintype "passive"))
      (node (ref "K2") (pin "3") (pinfunction "3_3") (pintype "passive"))
      (node (ref "K3") (pin "2") (pinfunction "2_2") (pintype "passive"))
      (node (ref "K4") (pin "2") (pinfunction "2_2") (pintype "passive"))
      (node (ref "K5") (pin "3") (pinfunction "3_3") (pintype "passive"))
      (node (ref "K6") (pin "SH1") (pinfunction "SH1_SH1") (pintype "passive"))
      (node (ref "K6") (pin "SH2") (pinfunction "SH1_SH2") (pintype "passive"))
      (node (ref "R12") (pin "2") (pinfunction "2_2") (pintype "passive"))
      (node (ref "R22") (pin "1") (pinfunction "1_1") (pintype "passive"))
      (node (ref "R23") (pin "1") (pinfunction "1_1") (pintype "passive"))
      (node (ref "R24") (pin "2") (pinfunction "2_2") (pintype "passive"))
      (node (ref "R28") (pin "2") (pinfunction "2_2") (pintype "passive"))
      (node (ref "R32") (pin "2") (pinfunction "2_2") (pintype "passive"))
      (node (ref "R6") (pin "1") (pinfunction "1_1") (pintype "passive"))
      (node (ref "X1") (pin "2") (pinfunction "G_2") (pintype "passive"))
      (node (ref "X1") (pin "4") (pinfunction "G_4") (pintype "passive"))
      (node (ref "X2") (pin "2") (pinfunction "G_2") (pintype "passive"))
      (node (ref "X2") (pin "4") (pinfunction "G_4") (pintype "passive"))
    )
    (net (code "31") (name "LED_CAN1") (class "Default")
      (node (ref "IC1") (pin "83") (pinfunction "PD2_83") (pintype "passive"))
      (node (ref "R5") (pin "2") (pinfunction "2_2") (pintype "passive"))
    )
    (net (code "32") (name "LED_CAN2") (class "Default")
      (node (ref "IC1") (pin "85") (pinfunction "PD4_85") (pintype "passive"))
      (node (ref "R7") (pin "2") (pinfunction "2_2") (pintype "passive"))
    )
    (net (code "33") (name "LED_GLOBAL") (class "Default")
      (node (ref "IC1") (pin "57") (pinfunction "PD10_57") (pintype "passive"))
      (node (ref "R9") (pin "2") (pinfunction "2_2") (pintype "passive"))
    )
    (net (code "34") (name "NRST") (class "Default")
      (node (ref "C19") (pin "1") (pinfunction "1_1") (pintype "passive"))
      (node (ref "IC1") (pin "14") (pinfunction "NRST_14") (pintype "passive"))
      (node (ref "K5") (pin "5") (pinfunction "5_5") (pintype "passive"))
      (node (ref "R26") (pin "1") (pinfunction "1_1") (pintype "passive"))
    )
    (net (code "35") (name "Net-(C1-Pad1)") (class "Default")
      (node (ref "C1") (pin "1") (pinfunction "1_1") (pintype "passive"))
      (node (ref "R1") (pin "1") (pinfunction "1_1") (pintype "passive"))
      (node (ref "R2") (pin "1") (pinfunction "1_1") (pintype "passive"))
      (node (ref "R3") (pin "1") (pinfunction "1_1") (pintype "passive"))
      (node (ref "R4") (pin "1") (pinfunction "1_1") (pintype "passive"))
    )
    (net (code "36") (name "Net-(C2-Pad2)") (class "Default")
      (node (ref "C2") (pin "2") (pinfunction "2_2") (pintype "passive"))
      (node (ref "K6") (pin "6") (pinfunction "6_6") (pintype "passive"))
    )
    (net (code "37") (name "Net-(C3-Pad2)") (class "Default")
      (node (ref "C3") (pin "2") (pinfunction "2_2") (pintype "passive"))
      (node (ref "K6") (pin "3") (pinfunction "3_3") (pintype "passive"))
    )
    (net (code "38") (name "Net-(C11-Pad2)") (class "Default")
      (node (ref "C11") (pin "2") (pinfunction "2_2") (pintype "passive"))
      (node (ref "C30") (pin "+") (pinfunction "+_+") (pintype "passive"))
      (node (ref "IC4") (pin "31") (pinfunction "VDD_1.2_31") (pintype "passive"))
      (node (ref "IC4") (pin "4") (pinfunction "VDD_1.2_4") (pintype "passive"))
    )
    (net (code "39") (name "Net-(C32-Pad2)") (class "Default")
      (node (ref "C32") (pin "2") (pinfunction "2_2") (pintype "passive"))
      (node (ref "JP2") (pin "2") (pinfunction "2_2") (pintype "passive"))
      (node (ref "JP2") (pin "4") (pinfunction "4_4") (pintype "passive"))
    )
    (net (code "40") (name "Net-(C33-Pad2)") (class "Default")
      (node (ref "C33") (pin "2") (pinfunction "2_2") (pintype "passive"))
      (node (ref "JP1") (pin "2") (pinfunction "2_2") (pintype "passive"))
      (node (ref "JP1") (pin "4") (pinfunction "4_4") (pintype "passive"))
    )
    (net (code "41") (name "Net-(C34-+)") (class "Default")
      (node (ref "C17") (pin "+") (pinfunction "+_+") (pintype "passive"))
      (node (ref "C18") (pin "+") (pinfunction "+_+") (pintype "passive"))
      (node (ref "C34") (pin "P") (pinfunction "+_P") (pintype "passive"))
      (node (ref "D4") (pin "K") (pinfunction "K_K") (pintype "passive"))
      (node (ref "IC5") (pin "7") (pinfunction "VIN_7") (pintype "passive"))
      (node (ref "K2") (pin "4") (pinfunction "4_4") (pintype "passive"))
    )
    (net (code "42") (name "Net-(D1-PadA)") (class "Default")
      (node (ref "D1") (pin "A") (pinfunction "A_A") (pintype "passive"))
      (node (ref "R10") (pin "2") (pinfunction "2_2") (pintype "passive"))
    )
    (net (code "43") (name "Net-(IC1-PH0)") (class "Default")
      (node (ref "C15") (pin "1") (pinfunction "1_1") (pintype "passive"))
      (node (ref "IC1") (pin "12") (pinfunction "PH0_12") (pintype "passive"))
      (node (ref "X2") (pin "1") (pinfunction "1_1") (pintype "passive"))
    )
    (net (code "44") (name "Net-(IC1-PH1)") (class "Default")
      (node (ref "C14") (pin "1") (pinfunction "1_1") (pintype "passive"))
      (node (ref "IC1") (pin "13") (pinfunction "PH1_13") (pintype "passive"))
      (node (ref "X2") (pin "3") (pinfunction "2_3") (pintype "passive"))
    )
    (net (code "45") (name "Net-(IC1-VCAP_1)") (class "Default")
      (node (ref "C7") (pin "+") (pinfunction "+_+") (pintype "passive"))
      (node (ref "IC1") (pin "49") (pinfunction "VCAP_1_49") (pintype "passive"))
    )
    (net (code "46") (name "Net-(IC1-VCAP_2)") (class "Default")
      (node (ref "C8") (pin "+") (pinfunction "+_+") (pintype "passive"))
      (node (ref "IC1") (pin "73") (pinfunction "VCAP_2_73") (pintype "passive"))
    )
    (net (code "47") (name "Net-(IC2A-CANH)") (class "Default")
      (node (ref "IC2") (pin "7") (pinfunction "CANH_7") (pintype "bidirectional"))
      (node (ref "K2") (pin "5") (pinfunction "5_5") (pintype "passive"))
      (node (ref "R15") (pin "2") (pinfunction "2_2") (pintype "passive"))
    )
    (net (code "48") (name "Net-(IC2A-CANL)") (class "Default")
      (node (ref "IC2") (pin "6") (pinfunction "CANL_6") (pintype "bidirectional"))
      (node (ref "K2") (pin "6") (pinfunction "6_6") (pintype "passive"))
      (node (ref "R13") (pin "2") (pinfunction "2_2") (pintype "passive"))
    )
    (net (code "49") (name "Net-(IC2A-RS)") (class "Default")
      (node (ref "IC2") (pin "8") (pinfunction "RS_8") (pintype "passive"))
      (node (ref "R28") (pin "1") (pinfunction "1_1") (pintype "passive"))
      (node (ref "R31") (pin "2") (pinfunction "2_2") (pintype "passive"))
      (node (ref "R33") (pin "2") (pinfunction "2_2") (pintype "passive"))
    )
    (net (code "50") (name "Net-(IC3A-CANH)") (class "Default")
      (node (ref "IC3") (pin "7") (pinfunction "CANH_7") (pintype "bidirectional"))
      (node (ref "K2") (pin "1") (pinfunction "1_1") (pintype "passive"))
      (node (ref "R14") (pin "2") (pinfunction "2_2") (pintype "passive"))
    )
    (net (code "51") (name "Net-(IC3A-CANL)") (class "Default")
      (node (ref "IC3") (pin "6") (pinfunction "CANL_6") (pintype "bidirectional"))
      (node (ref "K2") (pin "2") (pinfunction "2_2") (pintype "passive"))
      (node (ref "R16") (pin "2") (pinfunction "2_2") (pintype "passive"))
    )
    (net (code "52") (name "Net-(IC3A-RS)") (class "Default")
      (node (ref "IC3") (pin "8") (pinfunction "RS_8") (pintype "passive"))
      (node (ref "R29") (pin "2") (pinfunction "2_2") (pintype "passive"))
      (node (ref "R32") (pin "1") (pinfunction "1_1") (pintype "passive"))
      (node (ref "R34") (pin "2") (pinfunction "2_2") (pintype "passive"))
    )
    (net (code "53") (name "Net-(IC4-NWAYEN{slash}LED0)") (class "Default")
      (node (ref "IC4") (pin "42") (pinfunction "NWAYEN/LED0_42") (pintype "passive"))
      (node (ref "R21") (pin "1") (pinfunction "1_1") (pintype "passive"))
    )
    (net (code "54") (name "Net-(IC4-REXT)") (class "Default")
      (node (ref "IC4") (pin "16") (pinfunction "REXT_16") (pintype "passive"))
      (node (ref "R6") (pin "2") (pinfunction "2_2") (pintype "passive"))
    )
    (net (code "55") (name "Net-(IC4-RXM)") (class "Default")
      (node (ref "IC4") (pin "9") (pinfunction "RXM_9") (pintype "passive"))
      (node (ref "K6") (pin "8") (pinfunction "8_8") (pintype "passive"))
    )
    (net (code "56") (name "Net-(IC4-RXP)") (class "Default")
      (node (ref "IC4") (pin "10") (pinfunction "RXP_10") (pintype "passive"))
      (node (ref "K6") (pin "7") (pinfunction "7_7") (pintype "passive"))
    )
    (net (code "57") (name "Net-(IC4-SPEED{slash}LED1)") (class "Default")
      (node (ref "IC4") (pin "43") (pinfunction "SPEED/LED1_43") (pintype "passive"))
      (node (ref "R20") (pin "1") (pinfunction "1_1") (pintype "passive"))
    )
    (net (code "58") (name "Net-(IC4-TXM)") (class "Default")
      (node (ref "IC4") (pin "11") (pinfunction "TXM_11") (pintype "passive"))
      (node (ref "K6") (pin "2") (pinfunction "2_2") (pintype "passive"))
    )
    (net (code "59") (name "Net-(IC4-TXP)") (class "Default")
      (node (ref "IC4") (pin "12") (pinfunction "TXP_12") (pintype "passive"))
      (node (ref "K6") (pin "1") (pinfunction "1_1") (pintype "passive"))
    )
    (net (code "60") (name "Net-(IC4-VDDA_3.3)") (class "Default")
      (node (ref "C10") (pin "2") (pinfunction "2_2") (pintype "passive"))
      (node (ref "C26") (pin "+") (pinfunction "+_+") (pintype "passive"))
      (node (ref "IC4") (pin "7") (pinfunction "VDDA_3.3_7") (pintype "passive"))
      (node (ref "L1") (pin "2") (pinfunction "2_2") (pintype "passive"))
    )
    (net (code "61") (name "Net-(IC4-XI)") (class "Default")
      (node (ref "C5") (pin "2") (pinfunction "2_2") (pintype "passive"))
      (node (ref "IC4") (pin "15") (pinfunction "XI_15") (pintype "passive"))
      (node (ref "X1") (pin "1") (pinfunction "1_1") (pintype "passive"))
    )
    (net (code "62") (name "Net-(IC4-XO)") (class "Default")
      (node (ref "C6") (pin "2") (pinfunction "2_2") (pintype "passive"))
      (node (ref "IC4") (pin "14") (pinfunction "XO_14") (pintype "passive"))
      (node (ref "X1") (pin "3") (pinfunction "2_3") (pintype "passive"))
    )
    (net (code "63") (name "Net-(IC5-FB)") (class "Default")
      (node (ref "IC5") (pin "3") (pinfunction "NC3_3") (pintype "passive"))
      (node (ref "IC5") (pin "4") (pinfunction "FB_4") (pintype "passive"))
      (node (ref "R11") (pin "2") (pinfunction "2_2") (pintype "passive"))
      (node (ref "R12") (pin "1") (pinfunction "1_1") (pintype "passive"))
    )
    (net (code "64") (name "Net-(IC5-OUT)") (class "Default")
      (node (ref "D5") (pin "K") (pinfunction "K_K") (pintype "passive"))
      (node (ref "IC5") (pin "8") (pinfunction "OUT_8") (pintype "passive"))
      (node (ref "L2") (pin "1") (pinfunction "2_1") (pintype "passive"))
    )
    (net (code "65") (name "Net-(IC6A-Y)") (class "Default")
      (node (ref "D2") (pin "K") (pinfunction "K_K") (pintype "passive"))
      (node (ref "IC6") (pin "3") (pinfunction "Y_3") (pintype "output"))
      (node (ref "IC6") (pin "5") (pinfunction "A_5") (pintype "input"))
      (node (ref "R17") (pin "1") (pinfunction "1_1") (pintype "passive"))
    )
    (net (code "66") (name "Net-(IC6C-A)") (class "Default")
      (node (ref "D3") (pin "K") (pinfunction "K_K") (pintype "passive"))
      (node (ref "IC6") (pin "11") (pinfunction "Y_11") (pintype "output"))
      (node (ref "IC6") (pin "9") (pinfunction "A_9") (pintype "input"))
      (node (ref "R18") (pin "1") (pinfunction "1_1") (pintype "passive"))
    )
    (net (code "67") (name "Net-(JP1-Pad1)") (class "Default")
      (node (ref "JP1") (pin "1") (pinfunction "1_1") (pintype "passive"))
      (node (ref "R13") (pin "1") (pinfunction "1_1") (pintype "passive"))
    )
    (net (code "68") (name "Net-(JP1-Pad3)") (class "Default")
      (node (ref "JP1") (pin "3") (pinfunction "3_3") (pintype "passive"))
      (node (ref "R15") (pin "1") (pinfunction "1_1") (pintype "passive"))
    )
    (net (code "69") (name "Net-(JP2-Pad1)") (class "Default")
      (node (ref "JP2") (pin "1") (pinfunction "1_1") (pintype "passive"))
      (node (ref "R16") (pin "1") (pinfunction "1_1") (pintype "passive"))
    )
    (net (code "70") (name "Net-(JP2-Pad3)") (class "Default")
      (node (ref "JP2") (pin "3") (pinfunction "3_3") (pintype "passive"))
      (node (ref "R14") (pin "1") (pinfunction "1_1") (pintype "passive"))
    )
    (net (code "71") (name "Net-(K3-Pad1)") (class "Default")
      (node (ref "K3") (pin "1") (pinfunction "1_1") (pintype "passive"))
      (node (ref "K3") (pin "3") (pinfunction "3_3") (pintype "passive"))
      (node (ref "R17") (pin "2") (pinfunction "2_2") (pintype "passive"))
    )
    (net (code "72") (name "Net-(K4-Pad1)") (class "Default")
      (node (ref "K4") (pin "1") (pinfunction "1_1") (pintype "passive"))
      (node (ref "K4") (pin "3") (pinfunction "3_3") (pintype "passive"))
      (node (ref "R18") (pin "2") (pinfunction "2_2") (pintype "passive"))
    )
    (net (code "73") (name "Net-(K6-Pad4)") (class "Default")
      (node (ref "K6") (pin "4") (pinfunction "4_4") (pintype "passive"))
      (node (ref "R2") (pin "2") (pinfunction "2_2") (pintype "passive"))
    )
    (net (code "74") (name "Net-(K6-Pad5)") (class "Default")
      (node (ref "K6") (pin "5") (pinfunction "5_5") (pintype "passive"))
      (node (ref "R1") (pin "2") (pinfunction "2_2") (pintype "passive"))
    )
    (net (code "75") (name "Net-(K6-Pad9)") (class "Default")
      (node (ref "K6") (pin "9") (pinfunction "9_9") (pintype "passive"))
      (node (ref "R3") (pin "2") (pinfunction "2_2") (pintype "passive"))
    )
    (net (code "76") (name "Net-(K6-Pad10)") (class "Default")
      (node (ref "K6") (pin "10") (pinfunction "10_10") (pintype "passive"))
      (node (ref "R4") (pin "2") (pinfunction "2_2") (pintype "passive"))
    )
    (net (code "77") (name "Net-(K6B-K)") (class "Default")
      (node (ref "K6") (pin "K_Y") (pinfunction "K_K_Y") (pintype "passive"))
      (node (ref "R20") (pin "2") (pinfunction "2_2") (pintype "passive"))
    )
    (net (code "78") (name "Net-(K6C-K)") (class "Default")
      (node (ref "K6") (pin "K_G") (pinfunction "K_K_G") (pintype "passive"))
      (node (ref "R21") (pin "2") (pinfunction "2_2") (pintype "passive"))
    )
    (net (code "79") (name "Net-(LD1-C)") (class "Default")
      (node (ref "LD1") (pin "K") (pinfunction "C_K") (pintype "passive"))
      (node (ref "R5") (pin "1") (pinfunction "1_1") (pintype "passive"))
    )
    (net (code "80") (name "Net-(LD2-C)") (class "Default")
      (node (ref "LD2") (pin "K") (pinfunction "C_K") (pintype "passive"))
      (node (ref "R7") (pin "1") (pinfunction "1_1") (pintype "passive"))
    )
    (net (code "81") (name "Net-(LD3-C)") (class "Default")
      (node (ref "LD3") (pin "K") (pinfunction "C_K") (pintype "passive"))
      (node (ref "R9") (pin "1") (pinfunction "1_1") (pintype "passive"))
    )
    (net (code "82") (name "SWD_SWCLK") (class "Default")
      (node (ref "IC1") (pin "76") (pinfunction "PA14_76") (pintype "passive"))
      (node (ref "K5") (pin "2") (pinfunction "2_2") (pintype "passive"))
      (node (ref "R24") (pin "1") (pinfunction "1_1") (pintype "passive"))
    )
    (net (code "83") (name "SWD_SWDIO") (class "Default")
      (node (ref "IC1") (pin "72") (pinfunction "PA13_72") (pintype "passive"))
      (node (ref "K5") (pin "4") (pinfunction "4_4") (pintype "passive"))
      (node (ref "R25") (pin "2") (pinfunction "2_2") (pintype "passive"))
    )
    (net (code "84") (name "SWD_SWO") (class "Default")
      (node (ref "IC1") (pin "89") (pinfunction "PB3_89") (pintype "passive"))
      (node (ref "K5") (pin "6") (pinfunction "6_6") (pintype "passive"))
      (node (ref "R27") (pin "2") (pinfunction "2_2") (pintype "passive"))
    )
    (net (code "85") (name "TRIG1I") (class "Default")
      (node (ref "IC1") (pin "43") (pinfunction "PE12_43") (pintype "passive"))
      (node (ref "IC6") (pin "12") (pinfunction "A_12") (pintype "input"))
    )
    (net (code "86") (name "TRIG1O") (class "Default")
      (node (ref "IC1") (pin "42") (pinfunction "PE11_42") (pintype "passive"))
      (node (ref "IC6") (pin "8") (pinfunction "Y_8") (pintype "output"))
    )
    (net (code "87") (name "TRIG1OE") (class "Default")
      (node (ref "IC1") (pin "44") (pinfunction "PE13_44") (pintype "passive"))
      (node (ref "IC6") (pin "13") (pinfunction "OE_13") (pintype "input"))
    )
    (net (code "88") (name "TRIG2I") (class "Default")
      (node (ref "IC1") (pin "41") (pinfunction "PE10_41") (pintype "passive"))
      (node (ref "IC6") (pin "6") (pinfunction "Y_6") (pintype "output"))
    )
    (net (code "89") (name "TRIG2O") (class "Default")
      (node (ref "IC1") (pin "40") (pinfunction "PE9_40") (pintype "passive"))
      (node (ref "IC6") (pin "2") (pinfunction "A_2") (pintype "input"))
    )
    (net (code "90") (name "TRIG2OE") (class "Default")
      (node (ref "IC1") (pin "39") (pinfunction "PE8_39") (pintype "passive"))
      (node (ref "IC6") (pin "1") (pinfunction "OE_1") (pintype "input"))
    )
    (net (code "91") (name "USART3_RX") (class "Default")
      (node (ref "IC1") (pin "79") (pinfunction "PC11_79") (pintype "passive"))
      (node (ref "K1") (pin "4") (pinfunction "4_4") (pintype "passive"))
    )
    (net (code "92") (name "USART3_TX") (class "Default")
      (node (ref "IC1") (pin "78") (pinfunction "PC10_78") (pintype "passive"))
      (node (ref "K1") (pin "2") (pinfunction "2_2") (pintype "passive"))
    )
    (net (code "93") (name "unconnected-(IC1-PA4-Pad29)") (class "Default")
      (node (ref "IC1") (pin "29") (pinfunction "PA4_29") (pintype "passive"))
    )
    (net (code "94") (name "unconnected-(IC1-PA5-Pad30)") (class "Default")
      (node (ref "IC1") (pin "30") (pinfunction "PA5_30") (pintype "passive"))
    )
    (net (code "95") (name "unconnected-(IC1-PA6-Pad31)") (class "Default")
      (node (ref "IC1") (pin "31") (pinfunction "PA6_31") (pintype "passive"))
    )
    (net (code "96") (name "unconnected-(IC1-PA9-Pad68)") (class "Default")
      (node (ref "IC1") (pin "68") (pinfunction "PA9_68") (pintype "passive"))
    )
    (net (code "97") (name "unconnected-(IC1-PA10-Pad69)") (class "Default")
      (node (ref "IC1") (pin "69") (pinfunction "PA10_69") (pintype "passive"))
    )
    (net (code "98") (name "unconnected-(IC1-PA15-Pad77)") (class "Default")
      (node (ref "IC1") (pin "77") (pinfunction "PA15_77") (pintype "passive"))
    )
    (net (code "99") (name "unconnected-(IC1-PB4-Pad90)") (class "Default")
      (node (ref "IC1") (pin "90") (pinfunction "PB4_90") (pintype "passive"))
    )
    (net (code "100") (name "unconnected-(IC1-PB7-Pad93)") (class "Default")
      (node (ref "IC1") (pin "93") (pinfunction "PB7_93") (pintype "passive"))
    )
    (net (code "101") (name "unconnected-(IC1-PB8-Pad95)") (class "Default")
      (node (ref "IC1") (pin "95") (pinfunction "PB8_95") (pintype "passive"))
    )
    (net (code "102") (name "unconnected-(IC1-PB14-Pad53)") (class "Default")
      (node (ref "IC1") (pin "53") (pinfunction "PB14_53") (pintype "passive"))
    )
    (net (code "103") (name "unconnected-(IC1-PC0-Pad15)") (class "Default")
      (node (ref "IC1") (pin "15") (pinfunction "PC0_15") (pintype "passive"))
    )
    (net (code "104") (name "unconnected-(IC1-PC6-Pad63)") (class "Default")
      (node (ref "IC1") (pin "63") (pinfunction "PC6_63") (pintype "passive"))
    )
    (net (code "105") (name "unconnected-(IC1-PC7-Pad64)") (class "Default")
      (node (ref "IC1") (pin "64") (pinfunction "PC7_64") (pintype "passive"))
    )
    (net (code "106") (name "unconnected-(IC1-PC8-Pad65)") (class "Default")
      (node (ref "IC1") (pin "65") (pinfunction "PC8_65") (pintype "passive"))
    )
    (net (code "107") (name "unconnected-(IC1-PC9-Pad66)") (class "Default")
      (node (ref "IC1") (pin "66") (pinfunction "PC9_66") (pintype "passive"))
    )
    (net (code "108") (name "unconnected-(IC1-PC12-Pad80)") (class "Default")
      (node (ref "IC1") (pin "80") (pinfunction "PC12_80") (pintype "passive"))
    )
    (net (code "109") (name "unconnected-(IC1-PC13-Pad7)") (class "Default")
      (node (ref "IC1") (pin "7") (pinfunction "PC13_7") (pintype "passive"))
    )
    (net (code "110") (name "unconnected-(IC1-PC14-Pad8)") (class "Default")
      (node (ref "IC1") (pin "8") (pinfunction "PC14_8") (pintype "passive"))
    )
    (net (code "111") (name "unconnected-(IC1-PC15-Pad9)") (class "Default")
      (node (ref "IC1") (pin "9") (pinfunction "PC15_9") (pintype "passive"))
    )
    (net (code "112") (name "unconnected-(IC1-PD0-Pad81)") (class "Default")
      (node (ref "IC1") (pin "81") (pinfunction "PD0_81") (pintype "passive"))
    )
    (net (code "113") (name "unconnected-(IC1-PD1-Pad82)") (class "Default")
      (node (ref "IC1") (pin "82") (pinfunction "PD1_82") (pintype "passive"))
    )
    (net (code "114") (name "unconnected-(IC1-PD3-Pad84)") (class "Default")
      (node (ref "IC1") (pin "84") (pinfunction "PD3_84") (pintype "passive"))
    )
    (net (code "115") (name "unconnected-(IC1-PD5-Pad86)") (class "Default")
      (node (ref "IC1") (pin "86") (pinfunction "PD5_86") (pintype "passive"))
    )
    (net (code "116") (name "unconnected-(IC1-PD6-Pad87)") (class "Default")
      (node (ref "IC1") (pin "87") (pinfunction "PD6_87") (pintype "passive"))
    )
    (net (code "117") (name "unconnected-(IC1-PD7-Pad88)") (class "Default")
      (node (ref "IC1") (pin "88") (pinfunction "PD7_88") (pintype "passive"))
    )
    (net (code "118") (name "unconnected-(IC1-PD9-Pad56)") (class "Default")
      (node (ref "IC1") (pin "56") (pinfunction "PD9_56") (pintype "passive"))
    )
    (net (code "119") (name "unconnected-(IC1-PD11-Pad58)") (class "Default")
      (node (ref "IC1") (pin "58") (pinfunction "PD11_58") (pintype "passive"))
    )
    (net (code "120") (name "unconnected-(IC1-PD12-Pad59)") (class "Default")
      (node (ref "IC1") (pin "59") (pinfunction "PD12_59") (pintype "passive"))
    )
    (net (code "121") (name "unconnected-(IC1-PD13-Pad60)") (class "Default")
      (node (ref "IC1") (pin "60") (pinfunction "PD13_60") (pintype "passive"))
    )
    (net (code "122") (name "unconnected-(IC1-PD14-Pad61)") (class "Default")
      (node (ref "IC1") (pin "61") (pinfunction "PD14_61") (pintype "passive"))
    )
    (net (code "123") (name "unconnected-(IC1-PD15-Pad62)") (class "Default")
      (node (ref "IC1") (pin "62") (pinfunction "PD15_62") (pintype "passive"))
    )
    (net (code "124") (name "unconnected-(IC1-PE0-Pad97)") (class "Default")
      (node (ref "IC1") (pin "97") (pinfunction "PE0_97") (pintype "passive"))
    )
    (net (code "125") (name "unconnected-(IC1-PE1-Pad98)") (class "Default")
      (node (ref "IC1") (pin "98") (pinfunction "PE1_98") (pintype "passive"))
    )
    (net (code "126") (name "unconnected-(IC1-PE3-Pad2)") (class "Default")
      (node (ref "IC1") (pin "2") (pinfunction "PE3_2") (pintype "passive"))
    )
    (net (code "127") (name "unconnected-(IC1-PE4-Pad3)") (class "Default")
      (node (ref "IC1") (pin "3") (pinfunction "PE4_3") (pintype "passive"))
    )
    (net (code "128") (name "unconnected-(IC1-PE5-Pad4)") (class "Default")
      (node (ref "IC1") (pin "4") (pinfunction "PE5_4") (pintype "passive"))
    )
    (net (code "129") (name "unconnected-(IC1-PE6-Pad5)") (class "Default")
      (node (ref "IC1") (pin "5") (pinfunction "PE6_5") (pintype "passive"))
    )
    (net (code "130") (name "unconnected-(IC1-PE7-Pad38)") (class "Default")
      (node (ref "IC1") (pin "38") (pinfunction "PE7_38") (pintype "passive"))
    )
    (net (code "131") (name "unconnected-(IC1-PE14-Pad45)") (class "Default")
      (node (ref "IC1") (pin "45") (pinfunction "PE14_45") (pintype "passive"))
    )
    (net (code "132") (name "unconnected-(IC1-PE15-Pad46)") (class "Default")
      (node (ref "IC1") (pin "46") (pinfunction "PE15_46") (pintype "passive"))
    )
    (net (code "133") (name "unconnected-(IC2A-VREF-Pad5)") (class "Default")
      (node (ref "IC2") (pin "5") (pinfunction "VREF_5") (pintype "output"))
    )
    (net (code "134") (name "unconnected-(IC3A-VREF-Pad5)") (class "Default")
      (node (ref "IC3") (pin "5") (pinfunction "VREF_5") (pintype "output"))
    )
  )
)
